# S06.net
KiCad netlist of a schematic drawn in Altium Designer
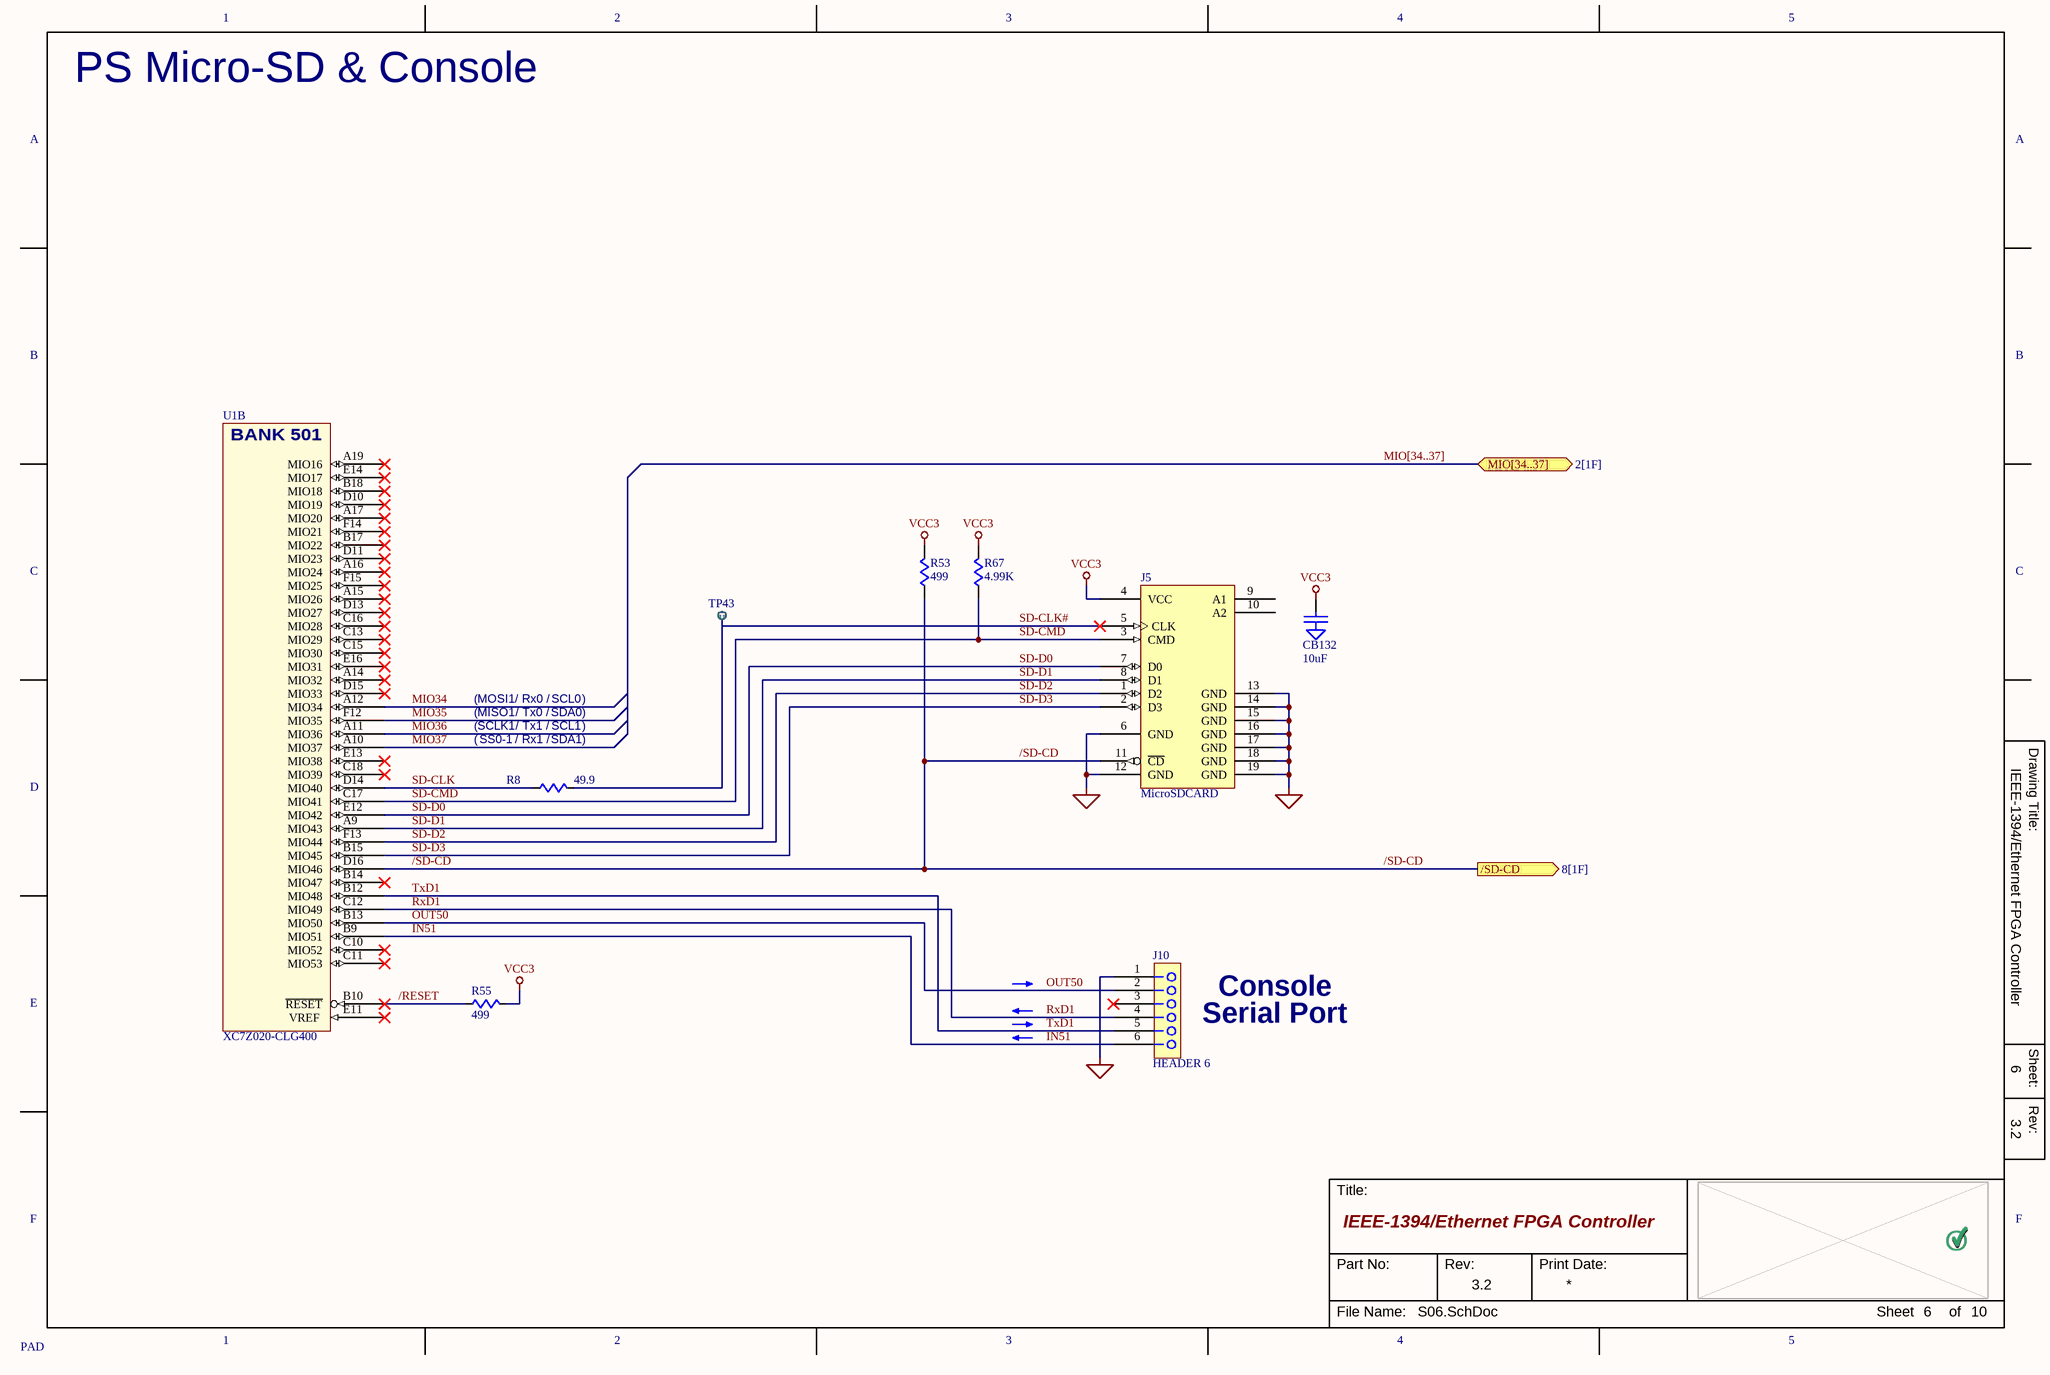
[diagram p0: S06.SchDoc]

(export (version "E")
  (design (tool "Eeschema 10.0.6"))
  (components
    (comp (ref "CB132") (value "10uF") (footprint "CB0603") (libsource (lib "LibJHU") (part "CAP-GND")))
    (comp (ref "J5")
      (value "MicroSDCARD")
      (footprint "CONN-uSD-JAE-ST12S0")
      (libsource (lib "LibJHU") (part "CONN-MICROSD-ST12S0"))
    )
    (comp (ref "J10")
      (value "HEADER 6")
      (footprint "HDR-6x1-100")
      (libsource (lib "LibJHU") (part "HEADER 6"))
    )
    (comp (ref "R8") (value "49.9") (footprint "R0201") (libsource (lib "LibJHU") (part "R")))
    (comp (ref "R53") (value "499") (footprint "R0402") (libsource (lib "") (part "R_1")))
    (comp (ref "R55") (value "499") (footprint "R0402") (libsource (lib "LibJHU") (part "R")))
    (comp (ref "R67") (value "4.99K") (footprint "R0402") (libsource (lib "") (part "R_1")))
    (comp (ref "TP43")
      (value "SD-CLK#")
      (footprint "PAD")
      (description "Test Point")
      (libsource (lib "Tomachie") (part "Tomachie_TP_North"))
    )
    (comp (ref "U1")
      (value "XC7Z020-CLG400")
      (footprint "BGA-400-08mm")
      (libsource (lib "LibJHU") (part "XC7Z020-CLG400"))
    )
  )
  (nets
    (net (code "1") (name "/IN51") (class "Default")
      (node (ref "J10") (pin "6") (pinfunction "6_6") (pintype "passive"))
      (node (ref "U1") (pin "B9") (pinfunction "MIO51_B9") (pintype "bidirectional"))
    )
    (net (code "2") (name "/MIO34") (class "Default")
      (node (ref "U1") (pin "A12") (pinfunction "MIO34_A12") (pintype "bidirectional"))
    )
    (net (code "3") (name "/MIO35") (class "Default")
      (node (ref "U1") (pin "F12") (pinfunction "MIO35_F12") (pintype "bidirectional"))
    )
    (net (code "4") (name "/MIO36") (class "Default")
      (node (ref "U1") (pin "A11") (pinfunction "MIO36_A11") (pintype "bidirectional"))
    )
    (net (code "5") (name "/MIO37") (class "Default")
      (node (ref "U1") (pin "A10") (pinfunction "MIO37_A10") (pintype "bidirectional"))
    )
    (net (code "7") (name "/OUT50") (class "Default")
      (node (ref "J10") (pin "2") (pinfunction "2_2") (pintype "passive"))
      (node (ref "U1") (pin "B13") (pinfunction "MIO50_B13") (pintype "bidirectional"))
    )
    (net (code "8") (name "/RxD1") (class "Default")
      (node (ref "J10") (pin "4") (pinfunction "4_4") (pintype "passive"))
      (node (ref "U1") (pin "C12") (pinfunction "MIO49_C12") (pintype "bidirectional"))
    )
    (net (code "9") (name "/SD-CLK") (class "Default")
      (node (ref "R8") (pin "1") (pinfunction "1_1") (pintype "passive"))
      (node (ref "U1") (pin "D14") (pinfunction "MIO40_D14") (pintype "bidirectional"))
    )
    (net (code "10") (name "/SD-CLK#") (class "Default")
      (node (ref "J5") (pin "5") (pinfunction "CLK_5") (pintype "input"))
      (node (ref "R8") (pin "2") (pinfunction "2_2") (pintype "passive"))
      (node (ref "TP43") (pin "1") (pinfunction "1_1") (pintype "passive"))
    )
    (net (code "11") (name "/SD-CMD") (class "Default")
      (node (ref "J5") (pin "3") (pinfunction "CMD_3") (pintype "input"))
      (node (ref "R67") (pin "1") (pinfunction "1_1") (pintype "passive"))
      (node (ref "U1") (pin "C17") (pinfunction "MIO41_C17") (pintype "bidirectional"))
    )
    (net (code "12") (name "/SD-D0") (class "Default")
      (node (ref "J5") (pin "7") (pinfunction "D0_7") (pintype "bidirectional"))
      (node (ref "U1") (pin "E12") (pinfunction "MIO42_E12") (pintype "bidirectional"))
    )
    (net (code "13") (name "/SD-D1") (class "Default")
      (node (ref "J5") (pin "8") (pinfunction "D1_8") (pintype "bidirectional"))
      (node (ref "U1") (pin "A9") (pinfunction "MIO43_A9") (pintype "bidirectional"))
    )
    (net (code "14") (name "/SD-D2") (class "Default")
      (node (ref "J5") (pin "1") (pinfunction "D2_1") (pintype "bidirectional"))
      (node (ref "U1") (pin "F13") (pinfunction "MIO44_F13") (pintype "bidirectional"))
    )
    (net (code "15") (name "/SD-D3") (class "Default")
      (node (ref "J5") (pin "2") (pinfunction "D3_2") (pintype "bidirectional"))
      (node (ref "U1") (pin "B15") (pinfunction "MIO45_B15") (pintype "bidirectional"))
    )
    (net (code "16") (name "/TxD1") (class "Default")
      (node (ref "J10") (pin "5") (pinfunction "5_5") (pintype "passive"))
      (node (ref "U1") (pin "B12") (pinfunction "MIO48_B12") (pintype "bidirectional"))
    )
    (net (code "17") (name "/{slash}RESET") (class "Default")
      (node (ref "R55") (pin "1") (pinfunction "1_1") (pintype "passive"))
      (node (ref "U1") (pin "B10") (pinfunction "RESET_B10") (pintype "input"))
    )
    (net (code "18") (name "/{slash}SD-CD") (class "Default")
      (node (ref "J5") (pin "11") (pinfunction "CD_11") (pintype "output"))
      (node (ref "R53") (pin "1") (pinfunction "1_1") (pintype "passive"))
      (node (ref "U1") (pin "D16") (pinfunction "MIO46_D16") (pintype "bidirectional"))
    )
    (net (code "19") (name "GND") (class "Default")
      (node (ref "CB132") (pin "2") (pinfunction "GND_2") (pintype "power_in"))
      (node (ref "J10") (pin "1") (pinfunction "1_1") (pintype "passive"))
      (node (ref "J5") (pin "12") (pinfunction "GND_12") (pintype "power_in"))
      (node (ref "J5") (pin "13") (pinfunction "GND_13") (pintype "power_in"))
      (node (ref "J5") (pin "14") (pinfunction "GND_14") (pintype "power_in"))
      (node (ref "J5") (pin "15") (pinfunction "GND_15") (pintype "power_in"))
      (node (ref "J5") (pin "16") (pinfunction "GND_16") (pintype "power_in"))
      (node (ref "J5") (pin "17") (pinfunction "GND_17") (pintype "power_in"))
      (node (ref "J5") (pin "18") (pinfunction "GND_18") (pintype "power_in"))
      (node (ref "J5") (pin "19") (pinfunction "GND_19") (pintype "power_in"))
      (node (ref "J5") (pin "6") (pinfunction "GND_6") (pintype "power_in"))
    )
    (net (code "20") (name "VCC3") (class "Default")
      (node (ref "CB132") (pin "1") (pintype "passive"))
      (node (ref "J5") (pin "4") (pinfunction "VCC_4") (pintype "power_in"))
      (node (ref "R53") (pin "2") (pinfunction "2_2") (pintype "passive"))
      (node (ref "R55") (pin "2") (pinfunction "2_2") (pintype "passive"))
      (node (ref "R67") (pin "2") (pinfunction "2_2") (pintype "passive"))
    )
    (net (code "21") (name "unconnected-(J5-A1-Pad9)") (class "Default")
      (node (ref "J5") (pin "9") (pinfunction "A1_9") (pintype "passive"))
    )
    (net (code "22") (name "unconnected-(J5-A2-Pad10)") (class "Default")
      (node (ref "J5") (pin "10") (pinfunction "A2_10") (pintype "passive"))
    )
    (net (code "23") (name "unconnected-(J10-Pad3)") (class "Default")
      (node (ref "J10") (pin "3") (pinfunction "3_3") (pintype "passive+no_connect"))
    )
    (net (code "24") (name "unconnected-(U1B-MIO16-PadA19)") (class "Default")
      (node (ref "U1") (pin "A19") (pinfunction "MIO16_A19") (pintype "bidirectional+no_connect"))
    )
    (net (code "25") (name "unconnected-(U1B-MIO17-PadE14)") (class "Default")
      (node (ref "U1") (pin "E14") (pinfunction "MIO17_E14") (pintype "bidirectional+no_connect"))
    )
    (net (code "26") (name "unconnected-(U1B-MIO18-PadB18)") (class "Default")
      (node (ref "U1") (pin "B18") (pinfunction "MIO18_B18") (pintype "bidirectional+no_connect"))
    )
    (net (code "27") (name "unconnected-(U1B-MIO19-PadD10)") (class "Default")
      (node (ref "U1") (pin "D10") (pinfunction "MIO19_D10") (pintype "bidirectional+no_connect"))
    )
    (net (code "28") (name "unconnected-(U1B-MIO20-PadA17)") (class "Default")
      (node (ref "U1") (pin "A17") (pinfunction "MIO20_A17") (pintype "bidirectional+no_connect"))
    )
    (net (code "29") (name "unconnected-(U1B-MIO21-PadF14)") (class "Default")
      (node (ref "U1") (pin "F14") (pinfunction "MIO21_F14") (pintype "bidirectional+no_connect"))
    )
    (net (code "30") (name "unconnected-(U1B-MIO22-PadB17)") (class "Default")
      (node (ref "U1") (pin "B17") (pinfunction "MIO22_B17") (pintype "bidirectional+no_connect"))
    )
    (net (code "31") (name "unconnected-(U1B-MIO23-PadD11)") (class "Default")
      (node (ref "U1") (pin "D11") (pinfunction "MIO23_D11") (pintype "bidirectional+no_connect"))
    )
    (net (code "32") (name "unconnected-(U1B-MIO24-PadA16)") (class "Default")
      (node (ref "U1") (pin "A16") (pinfunction "MIO24_A16") (pintype "bidirectional+no_connect"))
    )
    (net (code "33") (name "unconnected-(U1B-MIO25-PadF15)") (class "Default")
      (node (ref "U1") (pin "F15") (pinfunction "MIO25_F15") (pintype "bidirectional+no_connect"))
    )
    (net (code "34") (name "unconnected-(U1B-MIO26-PadA15)") (class "Default")
      (node (ref "U1") (pin "A15") (pinfunction "MIO26_A15") (pintype "bidirectional+no_connect"))
    )
    (net (code "35") (name "unconnected-(U1B-MIO27-PadD13)") (class "Default")
      (node (ref "U1") (pin "D13") (pinfunction "MIO27_D13") (pintype "bidirectional+no_connect"))
    )
    (net (code "36") (name "unconnected-(U1B-MIO28-PadC16)") (class "Default")
      (node (ref "U1") (pin "C16") (pinfunction "MIO28_C16") (pintype "bidirectional+no_connect"))
    )
    (net (code "37") (name "unconnected-(U1B-MIO29-PadC13)") (class "Default")
      (node (ref "U1") (pin "C13") (pinfunction "MIO29_C13") (pintype "bidirectional+no_connect"))
    )
    (net (code "38") (name "unconnected-(U1B-MIO30-PadC15)") (class "Default")
      (node (ref "U1") (pin "C15") (pinfunction "MIO30_C15") (pintype "bidirectional+no_connect"))
    )
    (net (code "39") (name "unconnected-(U1B-MIO31-PadE16)") (class "Default")
      (node (ref "U1") (pin "E16") (pinfunction "MIO31_E16") (pintype "bidirectional+no_connect"))
    )
    (net (code "40") (name "unconnected-(U1B-MIO32-PadA14)") (class "Default")
      (node (ref "U1") (pin "A14") (pinfunction "MIO32_A14") (pintype "bidirectional+no_connect"))
    )
    (net (code "41") (name "unconnected-(U1B-MIO33-PadD15)") (class "Default")
      (node (ref "U1") (pin "D15") (pinfunction "MIO33_D15") (pintype "bidirectional+no_connect"))
    )
    (net (code "42") (name "unconnected-(U1B-MIO38-PadE13)") (class "Default")
      (node (ref "U1") (pin "E13") (pinfunction "MIO38_E13") (pintype "bidirectional+no_connect"))
    )
    (net (code "43") (name "unconnected-(U1B-MIO39-PadC18)") (class "Default")
      (node (ref "U1") (pin "C18") (pinfunction "MIO39_C18") (pintype "bidirectional+no_connect"))
    )
    (net (code "44") (name "unconnected-(U1B-MIO47-PadB14)") (class "Default")
      (node (ref "U1") (pin "B14") (pinfunction "MIO47_B14") (pintype "bidirectional+no_connect"))
    )
    (net (code "45") (name "unconnected-(U1B-MIO52-PadC10)") (class "Default")
      (node (ref "U1") (pin "C10") (pinfunction "MIO52_C10") (pintype "bidirectional+no_connect"))
    )
    (net (code "46") (name "unconnected-(U1B-MIO53-PadC11)") (class "Default")
      (node (ref "U1") (pin "C11") (pinfunction "MIO53_C11") (pintype "bidirectional+no_connect"))
    )
    (net (code "47") (name "unconnected-(U1B-VREF-PadE11)") (class "Default")
      (node (ref "U1") (pin "E11") (pinfunction "VREF_E11") (pintype "input+no_connect"))
    )
  )
)
